# L-ink.net
KiCad netlist of a schematic drawn in Altium Designer
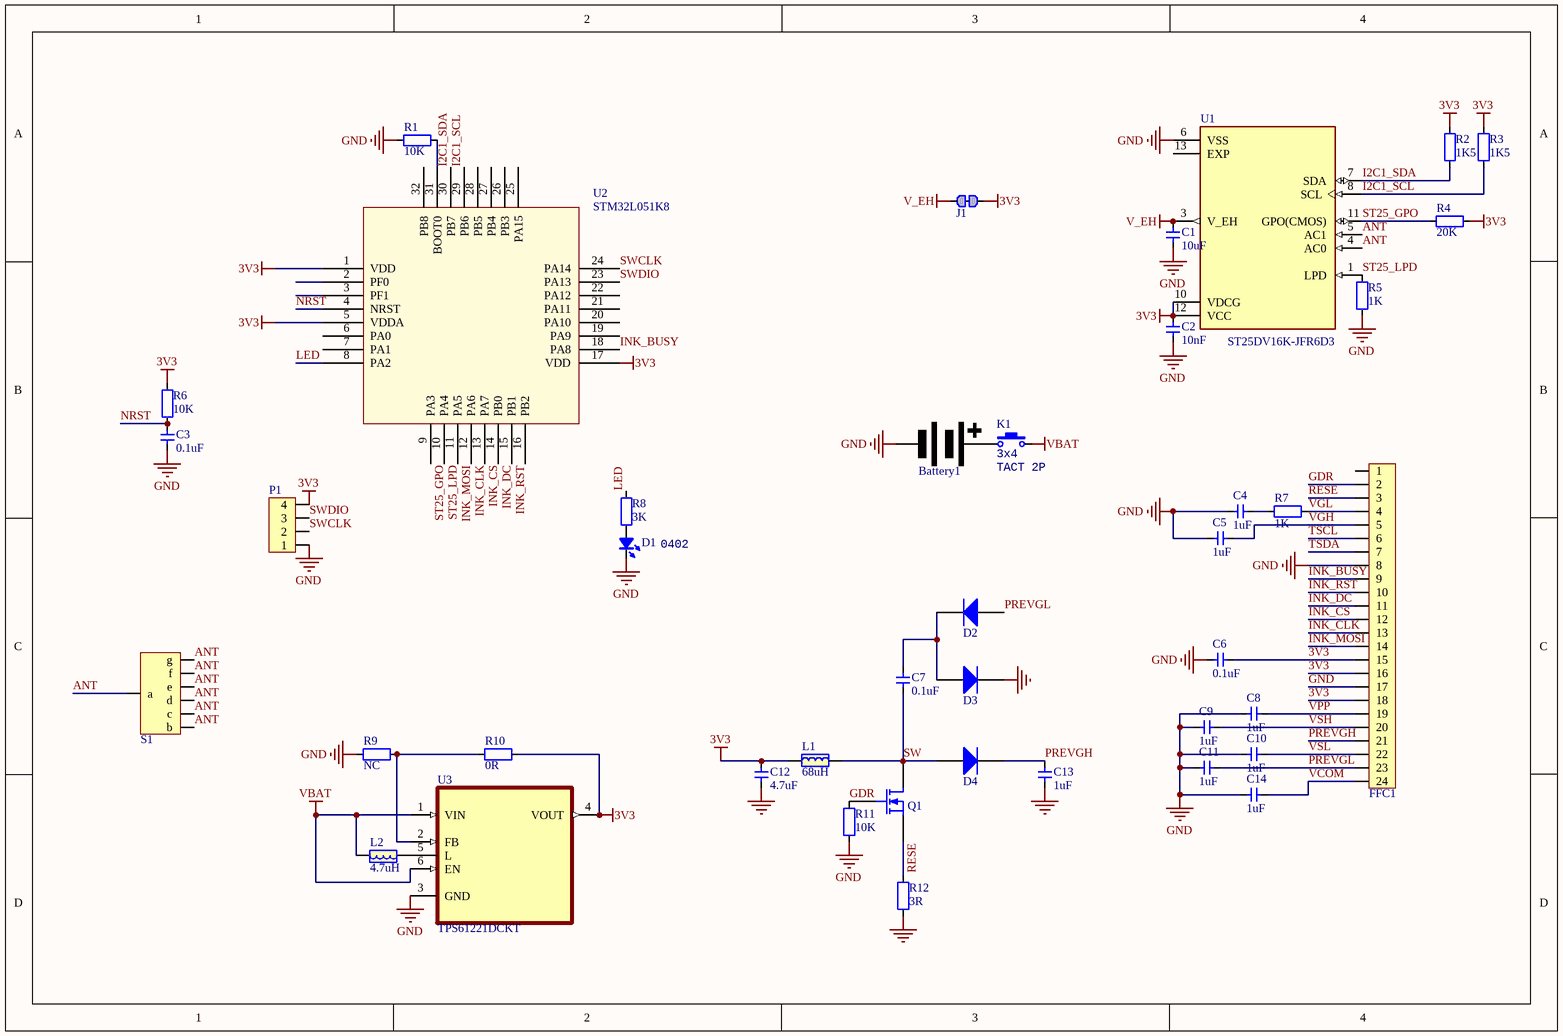
[diagram p0: L-ink.SchDoc]

(export (version "E")
  (design (tool "Eeschema 10.0.6"))
  (components
    (comp (ref "Battery1")
      (value "Battery")
      (footprint "CR2032-1")
      (libsource (lib "KitSprout") (part "Battery"))
    )
    (comp (ref "C1")
      (value "10uF")
      (footprint "CAP_0402")
      (description "Capacitor")
      (libsource (lib "MyPcbLib") (part "电容-0402"))
    )
    (comp (ref "C2")
      (value "10nF")
      (footprint "CAP_0402")
      (description "Capacitor")
      (libsource (lib "MyPcbLib") (part "电容-0402"))
    )
    (comp (ref "C3")
      (value "0.1uF")
      (footprint "CAP_0402")
      (description "Capacitor")
      (libsource (lib "MyPcbLib") (part "电容-0402"))
    )
    (comp (ref "C4")
      (value "1uF")
      (footprint "CAP_0402")
      (description "Capacitor")
      (libsource (lib "MyPcbLib") (part "电容-0402"))
    )
    (comp (ref "C5")
      (value "1uF")
      (footprint "CAP_0402")
      (description "Capacitor")
      (libsource (lib "MyPcbLib") (part "电容-0402"))
    )
    (comp (ref "C6")
      (value "0.1uF")
      (footprint "CAP_0402")
      (description "Capacitor")
      (libsource (lib "MyPcbLib") (part "电容-0402"))
    )
    (comp (ref "C7")
      (value "0.1uF")
      (footprint "CAP_0402")
      (description "Capacitor")
      (libsource (lib "MyPcbLib") (part "电容-0402"))
    )
    (comp (ref "C8")
      (value "1uF")
      (footprint "CAP_0402")
      (description "Capacitor")
      (libsource (lib "MyPcbLib") (part "电容-0402"))
    )
    (comp (ref "C9")
      (value "1uF")
      (footprint "CAP_0402")
      (description "Capacitor")
      (libsource (lib "MyPcbLib") (part "电容-0402"))
    )
    (comp (ref "C10")
      (value "1uF")
      (footprint "CAP_0402")
      (description "Capacitor")
      (libsource (lib "MyPcbLib") (part "电容-0402"))
    )
    (comp (ref "C11")
      (value "1uF")
      (footprint "CAP_0402")
      (description "Capacitor")
      (libsource (lib "MyPcbLib") (part "电容-0402"))
    )
    (comp (ref "C12")
      (value "4.7uF")
      (footprint "0603-CAP")
      (description "Capacitor")
      (libsource (lib "MyPcbLib") (part "电容-0603"))
    )
    (comp (ref "C13")
      (value "1uF")
      (footprint "CAP_0402")
      (description "Capacitor")
      (libsource (lib "MyPcbLib") (part "电容-0402"))
    )
    (comp (ref "C14")
      (value "1uF")
      (footprint "CAP_0402")
      (description "Capacitor")
      (libsource (lib "MyPcbLib") (part "电容-0402"))
    )
    (comp (ref "D1")
      (value "color?")
      (footprint "LED_0402_BLUE")
      (description "LED")
      (fields (field (name "TYPE") "0402"))
      (libsource (lib "KitSprout") (part "LED_0402"))
    )
    (comp (ref "D2")
      (value "二极管-5819W")
      (footprint "SOD-123")
      (description "40V")
      (libsource (lib "MyPcbLib") (part "二极管-5819W"))
    )
    (comp (ref "D3")
      (value "二极管-5819W")
      (footprint "SOD-123")
      (description "40V")
      (libsource (lib "MyPcbLib") (part "二极管-5819W"))
    )
    (comp (ref "D4")
      (value "二极管-5819W")
      (footprint "SOD-123")
      (description "40V")
      (libsource (lib "MyPcbLib") (part "二极管-5819W"))
    )
    (comp (ref "FFC1")
      (value "FFC_0.5_24")
      (footprint "FFC_0.5_24_INK")
      (description "FFC")
      (libsource (lib "MyPcbLib") (part "FFC_0.5_24_INK"))
    )
    (comp (ref "J1")
      (value "跳线")
      (footprint "0402-0R")
      (description "Resistor")
      (fields (field (name "PUBLISHER") "Altium Limited"))
      (libsource (lib "MyPcbLib") (part "跳线"))
    )
    (comp (ref "K1")
      (value "3x4")
      (footprint "ButtonTACT_3x4x2_180H")
      (description "Button")
      (fields (field (name "TYPE") "TACT 2P") (field (name "Comment") "TACT 2P"))
      (libsource (lib "KitSprout") (part "ButtonTACT_3x4x2_180"))
    )
    (comp (ref "L1")
      (value "68uH")
      (footprint "2520-L")
      (description "磁珠")
      (libsource (lib "MyPcbLib") (part "电感-2520"))
    )
    (comp (ref "L2")
      (value "4.7uH")
      (footprint "0805-L")
      (description "磁珠")
      (libsource (lib "MyPcbLib") (part "电感-0805"))
    )
    (comp (ref "P1")
      (value "HDR1x4_2.0")
      (footprint "HDR 4_2")
      (libsource (lib "MyPcbLib") (part "HDR1x4_2.0"))
    )
    (comp (ref "Q1")
      (value "MOSFET-N")
      (footprint "SOT23-3")
      (description "N-Channel MOSFET")
      (fields (field (name "PUBLISHER") "Altium Limited"))
      (libsource (lib "MyPcbLib") (part "MOSFET-N"))
    )
    (comp (ref "R1")
      (value "10K")
      (footprint "RES_0402")
      (description "Resistor")
      (libsource (lib "MyPcbLib") (part "电阻-0402"))
    )
    (comp (ref "R2")
      (value "1K5")
      (footprint "RES_0402")
      (description "Resistor")
      (libsource (lib "") (part "电阻-0402_2"))
    )
    (comp (ref "R3")
      (value "1K5")
      (footprint "RES_0402")
      (description "Resistor")
      (libsource (lib "") (part "电阻-0402_2"))
    )
    (comp (ref "R4")
      (value "20K")
      (footprint "RES_0402")
      (description "Resistor")
      (libsource (lib "MyPcbLib") (part "电阻-0402"))
    )
    (comp (ref "R5")
      (value "1K")
      (footprint "RES_0402")
      (description "Resistor")
      (libsource (lib "") (part "电阻-0402_2"))
    )
    (comp (ref "R6")
      (value "10K")
      (footprint "RES_0402")
      (description "Resistor")
      (libsource (lib "") (part "电阻-0402_1"))
    )
    (comp (ref "R7")
      (value "1K")
      (footprint "RES_0402")
      (description "Resistor")
      (libsource (lib "MyPcbLib") (part "电阻-0402"))
    )
    (comp (ref "R8")
      (value "3K")
      (footprint "RES_0402")
      (description "Resistor")
      (libsource (lib "") (part "电阻-0402_1"))
    )
    (comp (ref "R9")
      (value "NC")
      (footprint "RES_0402")
      (description "Resistor")
      (libsource (lib "MyPcbLib") (part "电阻-0402"))
    )
    (comp (ref "R10")
      (value "0R")
      (footprint "RES_0402")
      (description "Resistor")
      (libsource (lib "MyPcbLib") (part "电阻-0402"))
    )
    (comp (ref "R11")
      (value "10K")
      (footprint "RES_0402")
      (description "Resistor")
      (libsource (lib "") (part "电阻-0402_1"))
    )
    (comp (ref "R12")
      (value "3R")
      (footprint "RES_0402")
      (description "Resistor")
      (libsource (lib "") (part "电阻-0402_1"))
    )
    (comp (ref "S1")
      (value "WHEEL_SWITCH")
      (footprint "WHEEL_SWITCH")
      (description "LDO")
      (libsource (lib "MyPcbLib") (part "WHEEL_SWITCH"))
    )
    (comp (ref "U1")
      (value "ST25DV16K-JFR6D3")
      (footprint "PSON50P-302X302X60-13N")
      (description "RFID Transponder IC 13.56MHz ISO 15693 IÂ²C 1.8V ~ 5.5V 12-UFDFN Exposed Pad")
      (fields (field (name "MF") "STMicroelectronics"))
      (libsource (lib "MyPcbLib") (part "ST25DV16K-JFR6D3"))
    )
    (comp (ref "U2")
      (value "STM32L051K8")
      (footprint "QFN-32")
      (libsource (lib "MyPcbLib") (part "STM32L051K8"))
    )
    (comp (ref "U3")
      (value "TPS61221DCKT")
      (footprint "SOT65P210X110-6N")
      (description "Boost Switching Regulator IC Positive Fixed 3.3V 1 Output 200mA _Switch_ 6-TSSOP, SC-88, SOT-363")
      (fields (field (name "MP") "TPS61221DCK") (field (name "MF") "Texas Instruments"))
      (libsource (lib "MyPcbLib") (part "TPS61221DCKT"))
    )
  )
  (nets
    (net (code "1") (name "/ANT") (class "Default")
      (node (ref "S1") (pin "a") (pinfunction "a_a") (pintype "power_in"))
      (node (ref "S1") (pin "b") (pinfunction "b_b") (pintype "power_in"))
      (node (ref "S1") (pin "c") (pinfunction "c_c") (pintype "power_in"))
      (node (ref "S1") (pin "d") (pinfunction "d_d") (pintype "power_in"))
      (node (ref "S1") (pin "e") (pinfunction "e_e") (pintype "power_in"))
      (node (ref "S1") (pin "f") (pinfunction "f_f") (pintype "power_in"))
      (node (ref "S1") (pin "g") (pinfunction "g_g") (pintype "power_in"))
      (node (ref "U1") (pin "4") (pinfunction "AC0_4") (pintype "input"))
      (node (ref "U1") (pin "5") (pinfunction "AC1_5") (pintype "input"))
    )
    (net (code "2") (name "/GDR") (class "Default")
      (node (ref "FFC1") (pin "2") (pinfunction "2_2") (pintype "passive"))
      (node (ref "Q1") (pin "1") (pinfunction "G_1") (pintype "passive"))
      (node (ref "R11") (pin "2") (pinfunction "2_2") (pintype "passive"))
    )
    (net (code "3") (name "/I2C1_SCL") (class "Default")
      (node (ref "R3") (pin "2") (pinfunction "2_2") (pintype "passive"))
      (node (ref "U1") (pin "8") (pinfunction "SCL_8") (pintype "input"))
      (node (ref "U2") (pin "29") (pinfunction "PB6_29") (pintype "passive"))
    )
    (net (code "4") (name "/I2C1_SDA") (class "Default")
      (node (ref "R2") (pin "2") (pinfunction "2_2") (pintype "passive"))
      (node (ref "U1") (pin "7") (pinfunction "SDA_7") (pintype "bidirectional"))
      (node (ref "U2") (pin "30") (pinfunction "PB7_30") (pintype "passive"))
    )
    (net (code "5") (name "/INK_BUSY") (class "Default")
      (node (ref "FFC1") (pin "9") (pinfunction "9_9") (pintype "passive"))
      (node (ref "U2") (pin "18") (pinfunction "PA8_18") (pintype "passive"))
    )
    (net (code "6") (name "/INK_CLK") (class "Default")
      (node (ref "FFC1") (pin "13") (pinfunction "13_13") (pintype "passive"))
      (node (ref "U2") (pin "12") (pinfunction "PA6_12") (pintype "passive"))
    )
    (net (code "7") (name "/INK_CS") (class "Default")
      (node (ref "FFC1") (pin "12") (pinfunction "12_12") (pintype "passive"))
      (node (ref "U2") (pin "13") (pinfunction "PA7_13") (pintype "passive"))
    )
    (net (code "8") (name "/INK_DC") (class "Default")
      (node (ref "FFC1") (pin "11") (pinfunction "11_11") (pintype "passive"))
      (node (ref "U2") (pin "14") (pinfunction "PB0_14") (pintype "passive"))
    )
    (net (code "9") (name "/INK_MOSI") (class "Default")
      (node (ref "FFC1") (pin "14") (pinfunction "14_14") (pintype "passive"))
      (node (ref "U2") (pin "11") (pinfunction "PA5_11") (pintype "passive"))
    )
    (net (code "10") (name "/INK_RST") (class "Default")
      (node (ref "FFC1") (pin "10") (pinfunction "10_10") (pintype "passive"))
      (node (ref "U2") (pin "15") (pinfunction "PB1_15") (pintype "passive"))
    )
    (net (code "11") (name "/LED") (class "Default")
      (node (ref "R8") (pin "2") (pinfunction "2_2") (pintype "passive"))
      (node (ref "U2") (pin "8") (pinfunction "PA2_8") (pintype "passive"))
    )
    (net (code "12") (name "/NRST") (class "Default")
      (node (ref "C3") (pin "1") (pinfunction "1_1") (pintype "passive"))
      (node (ref "R6") (pin "1") (pinfunction "1_1") (pintype "passive"))
      (node (ref "U2") (pin "4") (pinfunction "NRST_4") (pintype "passive"))
    )
    (net (code "13") (name "/PREVGH") (class "Default")
      (node (ref "C13") (pin "1") (pinfunction "1_1") (pintype "passive"))
      (node (ref "D4") (pin "2") (pinfunction "K_2") (pintype "passive"))
      (node (ref "FFC1") (pin "21") (pinfunction "21_21") (pintype "passive"))
    )
    (net (code "14") (name "/PREVGL") (class "Default")
      (node (ref "C11") (pin "2") (pinfunction "2_2") (pintype "passive"))
      (node (ref "D2") (pin "1") (pinfunction "A_1") (pintype "passive"))
      (node (ref "FFC1") (pin "23") (pinfunction "23_23") (pintype "passive"))
    )
    (net (code "15") (name "/RESE") (class "Default")
      (node (ref "FFC1") (pin "3") (pinfunction "3_3") (pintype "passive"))
      (node (ref "Q1") (pin "2") (pinfunction "S_2") (pintype "passive"))
      (node (ref "R12") (pin "2") (pinfunction "2_2") (pintype "passive"))
    )
    (net (code "16") (name "/ST25_GPO") (class "Default")
      (node (ref "R4") (pin "2") (pinfunction "2_2") (pintype "passive"))
      (node (ref "U1") (pin "11") (pinfunction "GPO(CMOS)_11") (pintype "bidirectional"))
      (node (ref "U2") (pin "9") (pinfunction "PA3_9") (pintype "passive"))
    )
    (net (code "17") (name "/ST25_LPD") (class "Default")
      (node (ref "R5") (pin "1") (pinfunction "1_1") (pintype "passive"))
      (node (ref "U1") (pin "1") (pinfunction "LPD_1") (pintype "input"))
      (node (ref "U2") (pin "10") (pinfunction "PA4_10") (pintype "passive"))
    )
    (net (code "18") (name "/SW") (class "Default")
      (node (ref "C7") (pin "2") (pinfunction "2_2") (pintype "passive"))
      (node (ref "D4") (pin "1") (pinfunction "A_1") (pintype "passive"))
      (node (ref "L1") (pin "2") (pinfunction "2_2") (pintype "passive"))
      (node (ref "Q1") (pin "3") (pinfunction "D_3") (pintype "passive"))
    )
    (net (code "19") (name "/SWCLK") (class "Default")
      (node (ref "P1") (pin "2") (pinfunction "2_2") (pintype "passive"))
      (node (ref "U2") (pin "24") (pinfunction "PA14_24") (pintype "passive"))
    )
    (net (code "20") (name "/SWDIO") (class "Default")
      (node (ref "P1") (pin "3") (pinfunction "3_3") (pintype "passive"))
      (node (ref "U2") (pin "23") (pinfunction "PA13_23") (pintype "passive"))
    )
    (net (code "21") (name "/TSCL") (class "Default")
      (node (ref "FFC1") (pin "6") (pinfunction "6_6") (pintype "passive"))
    )
    (net (code "22") (name "/TSDA") (class "Default")
      (node (ref "FFC1") (pin "7") (pinfunction "7_7") (pintype "passive"))
    )
    (net (code "23") (name "/VCOM") (class "Default")
      (node (ref "C14") (pin "2") (pinfunction "2_2") (pintype "passive"))
      (node (ref "FFC1") (pin "24") (pinfunction "24_24") (pintype "passive"))
    )
    (net (code "24") (name "/VGH") (class "Default")
      (node (ref "C5") (pin "2") (pinfunction "2_2") (pintype "passive"))
      (node (ref "FFC1") (pin "5") (pinfunction "5_5") (pintype "passive"))
    )
    (net (code "25") (name "/VGL") (class "Default")
      (node (ref "FFC1") (pin "4") (pinfunction "4_4") (pintype "passive"))
      (node (ref "R7") (pin "1") (pinfunction "1_1") (pintype "passive"))
    )
    (net (code "26") (name "/VPP") (class "Default")
      (node (ref "C8") (pin "2") (pinfunction "2_2") (pintype "passive"))
      (node (ref "FFC1") (pin "19") (pinfunction "19_19") (pintype "passive"))
    )
    (net (code "27") (name "/VSH") (class "Default")
      (node (ref "C9") (pin "2") (pinfunction "2_2") (pintype "passive"))
      (node (ref "FFC1") (pin "20") (pinfunction "20_20") (pintype "passive"))
    )
    (net (code "28") (name "/VSL") (class "Default")
      (node (ref "C10") (pin "2") (pinfunction "2_2") (pintype "passive"))
      (node (ref "FFC1") (pin "22") (pinfunction "22_22") (pintype "passive"))
    )
    (net (code "29") (name "3V3") (class "Default")
      (node (ref "C12") (pin "1") (pinfunction "1_1") (pintype "passive"))
      (node (ref "C2") (pin "1") (pinfunction "1_1") (pintype "passive"))
      (node (ref "C6") (pin "2") (pinfunction "2_2") (pintype "passive"))
      (node (ref "FFC1") (pin "15") (pinfunction "15_15") (pintype "passive"))
      (node (ref "FFC1") (pin "16") (pinfunction "16_16") (pintype "passive"))
      (node (ref "FFC1") (pin "18") (pinfunction "18_18") (pintype "passive"))
      (node (ref "J1") (pin "2") (pinfunction "2_2") (pintype "passive"))
      (node (ref "L1") (pin "1") (pintype "passive"))
      (node (ref "P1") (pin "4") (pinfunction "4_4") (pintype "passive"))
      (node (ref "R10") (pin "1") (pinfunction "1_1") (pintype "passive"))
      (node (ref "R2") (pin "1") (pinfunction "1_1") (pintype "passive"))
      (node (ref "R3") (pin "1") (pinfunction "1_1") (pintype "passive"))
      (node (ref "R4") (pin "1") (pinfunction "1_1") (pintype "passive"))
      (node (ref "R6") (pin "2") (pinfunction "2_2") (pintype "passive"))
      (node (ref "U1") (pin "10") (pinfunction "VDCG_10") (pintype "power_in"))
      (node (ref "U1") (pin "12") (pinfunction "VCC_12") (pintype "power_in"))
      (node (ref "U2") (pin "1") (pinfunction "VDD_1") (pintype "passive"))
      (node (ref "U2") (pin "17") (pinfunction "VDD_17") (pintype "passive"))
      (node (ref "U2") (pin "5") (pinfunction "VDDA_5") (pintype "passive"))
      (node (ref "U3") (pin "4") (pinfunction "VOUT_4") (pintype "output"))
    )
    (net (code "30") (name "GND") (class "Default")
      (node (ref "Battery1") (pin "1") (pinfunction "-_1") (pintype "passive"))
      (node (ref "C1") (pin "2") (pinfunction "2_2") (pintype "passive"))
      (node (ref "C10") (pin "1") (pinfunction "1_1") (pintype "passive"))
      (node (ref "C11") (pin "1") (pinfunction "1_1") (pintype "passive"))
      (node (ref "C12") (pin "2") (pinfunction "2_2") (pintype "passive"))
      (node (ref "C13") (pin "2") (pinfunction "2_2") (pintype "passive"))
      (node (ref "C14") (pin "1") (pinfunction "1_1") (pintype "passive"))
      (node (ref "C2") (pin "2") (pinfunction "2_2") (pintype "passive"))
      (node (ref "C3") (pin "2") (pinfunction "2_2") (pintype "passive"))
      (node (ref "C4") (pin "1") (pinfunction "1_1") (pintype "passive"))
      (node (ref "C5") (pin "1") (pinfunction "1_1") (pintype "passive"))
      (node (ref "C6") (pin "1") (pinfunction "1_1") (pintype "passive"))
      (node (ref "C8") (pin "1") (pinfunction "1_1") (pintype "passive"))
      (node (ref "C9") (pin "1") (pinfunction "1_1") (pintype "passive"))
      (node (ref "D1") (pin "2") (pinfunction "K_2") (pintype "passive"))
      (node (ref "D3") (pin "2") (pinfunction "K_2") (pintype "passive"))
      (node (ref "FFC1") (pin "17") (pinfunction "17_17") (pintype "passive"))
      (node (ref "FFC1") (pin "8") (pinfunction "8_8") (pintype "passive"))
      (node (ref "P1") (pin "1") (pinfunction "1_1") (pintype "passive"))
      (node (ref "R1") (pin "2") (pinfunction "2_2") (pintype "passive"))
      (node (ref "R11") (pin "1") (pinfunction "1_1") (pintype "passive"))
      (node (ref "R12") (pin "1") (pinfunction "1_1") (pintype "passive"))
      (node (ref "R5") (pin "2") (pinfunction "2_2") (pintype "passive"))
      (node (ref "R9") (pin "2") (pinfunction "2_2") (pintype "passive"))
      (node (ref "U1") (pin "6") (pinfunction "VSS_6") (pintype "power_in"))
      (node (ref "U3") (pin "3") (pinfunction "GND_3") (pintype "passive"))
    )
    (net (code "31") (name "Net-(Battery1-+)") (class "Default")
      (node (ref "Battery1") (pin "2") (pinfunction "+_2") (pintype "passive"))
      (node (ref "K1") (pin "1") (pinfunction "1_1") (pintype "passive"))
    )
    (net (code "32") (name "Net-(C4-Pad2)") (class "Default")
      (node (ref "C4") (pin "2") (pinfunction "2_2") (pintype "passive"))
      (node (ref "R7") (pin "2") (pinfunction "2_2") (pintype "passive"))
    )
    (net (code "33") (name "Net-(D1-A)") (class "Default")
      (node (ref "D1") (pin "1") (pinfunction "A_1") (pintype "passive"))
      (node (ref "R8") (pin "1") (pinfunction "1_1") (pintype "passive"))
    )
    (net (code "34") (name "Net-(D2-K)") (class "Default")
      (node (ref "C7") (pin "1") (pinfunction "1_1") (pintype "passive"))
      (node (ref "D2") (pin "2") (pinfunction "K_2") (pintype "passive"))
      (node (ref "D3") (pin "1") (pinfunction "A_1") (pintype "passive"))
    )
    (net (code "35") (name "Net-(U2-BOOT0)") (class "Default")
      (node (ref "R1") (pin "1") (pinfunction "1_1") (pintype "passive"))
      (node (ref "U2") (pin "31") (pinfunction "BOOT0_31") (pintype "passive"))
    )
    (net (code "36") (name "Net-(U3-FB)") (class "Default")
      (node (ref "R10") (pin "2") (pinfunction "2_2") (pintype "passive"))
      (node (ref "R9") (pin "1") (pinfunction "1_1") (pintype "passive"))
      (node (ref "U3") (pin "2") (pinfunction "FB_2") (pintype "input"))
    )
    (net (code "37") (name "Net-(U3-L)") (class "Default")
      (node (ref "L2") (pin "1") (pintype "passive"))
      (node (ref "U3") (pin "5") (pinfunction "L_5") (pintype "passive"))
    )
    (net (code "38") (name "VBAT") (class "Default")
      (node (ref "K1") (pin "2") (pinfunction "2_2") (pintype "passive"))
      (node (ref "L2") (pin "2") (pinfunction "2_2") (pintype "passive"))
      (node (ref "U3") (pin "1") (pinfunction "VIN_1") (pintype "input"))
      (node (ref "U3") (pin "6") (pinfunction "EN_6") (pintype "input"))
    )
    (net (code "39") (name "V_EH") (class "Default")
      (node (ref "C1") (pin "1") (pinfunction "1_1") (pintype "passive"))
      (node (ref "J1") (pin "1") (pinfunction "1_1") (pintype "passive"))
      (node (ref "U1") (pin "3") (pinfunction "V_EH_3") (pintype "output"))
    )
    (net (code "40") (name "unconnected-(FFC1-Pad1)") (class "Default")
      (node (ref "FFC1") (pin "1") (pinfunction "1_1") (pintype "passive"))
    )
    (net (code "41") (name "unconnected-(U1-EXP-Pad13)") (class "Default")
      (node (ref "U1") (pin "13") (pinfunction "EXP_13") (pintype "power_in"))
    )
    (net (code "42") (name "unconnected-(U2-PA0-Pad6)") (class "Default")
      (node (ref "U2") (pin "6") (pinfunction "PA0_6") (pintype "passive"))
    )
    (net (code "43") (name "unconnected-(U2-PA1-Pad7)") (class "Default")
      (node (ref "U2") (pin "7") (pinfunction "PA1_7") (pintype "passive"))
    )
    (net (code "44") (name "unconnected-(U2-PA9-Pad19)") (class "Default")
      (node (ref "U2") (pin "19") (pinfunction "PA9_19") (pintype "passive"))
    )
    (net (code "45") (name "unconnected-(U2-PA10-Pad20)") (class "Default")
      (node (ref "U2") (pin "20") (pinfunction "PA10_20") (pintype "passive"))
    )
    (net (code "46") (name "unconnected-(U2-PA11-Pad21)") (class "Default")
      (node (ref "U2") (pin "21") (pinfunction "PA11_21") (pintype "passive"))
    )
    (net (code "47") (name "unconnected-(U2-PA12-Pad22)") (class "Default")
      (node (ref "U2") (pin "22") (pinfunction "PA12_22") (pintype "passive"))
    )
    (net (code "48") (name "unconnected-(U2-PA15-Pad25)") (class "Default")
      (node (ref "U2") (pin "25") (pinfunction "PA15_25") (pintype "passive"))
    )
    (net (code "49") (name "unconnected-(U2-PB2-Pad16)") (class "Default")
      (node (ref "U2") (pin "16") (pinfunction "PB2_16") (pintype "passive"))
    )
    (net (code "50") (name "unconnected-(U2-PB3-Pad26)") (class "Default")
      (node (ref "U2") (pin "26") (pinfunction "PB3_26") (pintype "passive"))
    )
    (net (code "51") (name "unconnected-(U2-PB4-Pad27)") (class "Default")
      (node (ref "U2") (pin "27") (pinfunction "PB4_27") (pintype "passive"))
    )
    (net (code "52") (name "unconnected-(U2-PB5-Pad28)") (class "Default")
      (node (ref "U2") (pin "28") (pinfunction "PB5_28") (pintype "passive"))
    )
    (net (code "53") (name "unconnected-(U2-PB8-Pad32)") (class "Default")
      (node (ref "U2") (pin "32") (pinfunction "PB8_32") (pintype "passive"))
    )
    (net (code "54") (name "unconnected-(U2-PF0-Pad2)") (class "Default")
      (node (ref "U2") (pin "2") (pinfunction "PF0_2") (pintype "passive"))
    )
    (net (code "55") (name "unconnected-(U2-PF1-Pad3)") (class "Default")
      (node (ref "U2") (pin "3") (pinfunction "PF1_3") (pintype "passive"))
    )
  )
)
